# Mixer.net
KiCad netlist of a schematic drawn in EasyEDA Pro
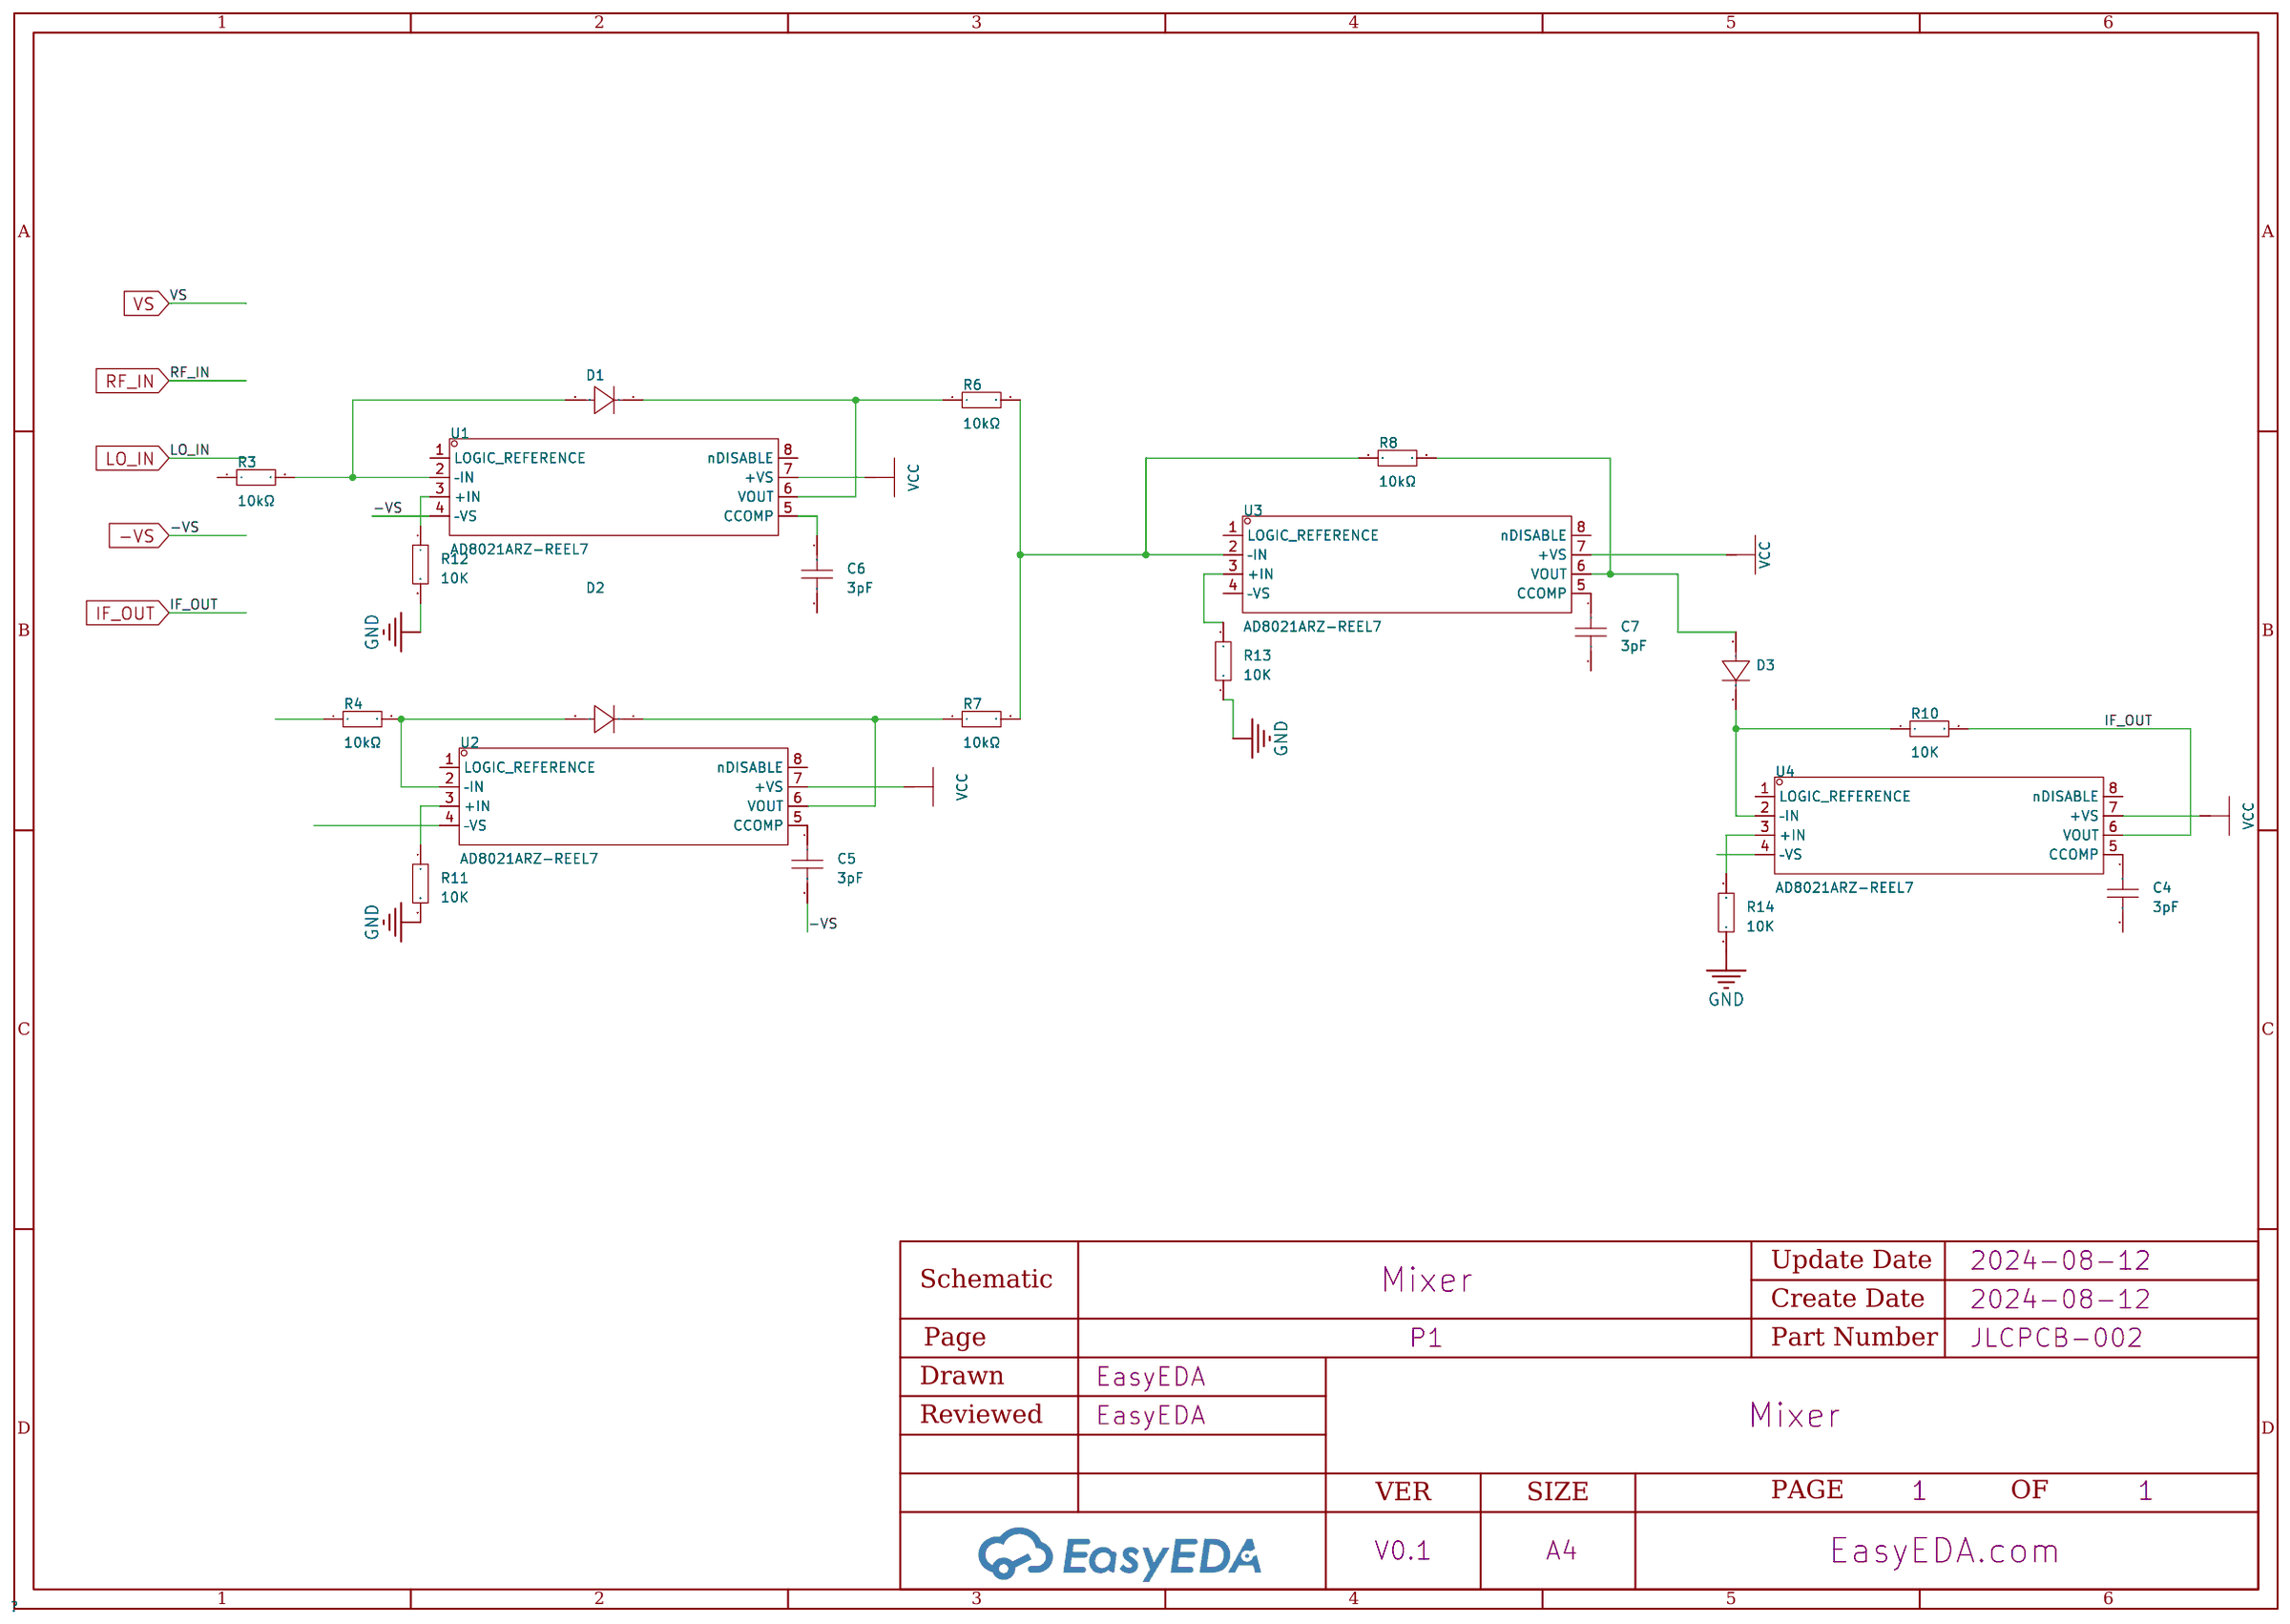
[diagram p0: schematic sheet]

(export (version "E")
  (design (tool "Eeschema 10.0.6"))
  (components
    (comp (ref "C4") (value "3pF") (footprint "easyedapro:C0201") (libsource (lib "easyedapro") (part "CAP")))
    (comp (ref "C5") (value "3pF") (footprint "easyedapro:C0201") (libsource (lib "easyedapro") (part "CAP")))
    (comp (ref "C6") (value "3pF") (footprint "easyedapro:C0201") (libsource (lib "easyedapro") (part "CAP")))
    (comp (ref "C7") (value "3pF") (footprint "easyedapro:C0201") (libsource (lib "easyedapro") (part "CAP")))
    (comp (ref "D1")
      (value "~")
      (footprint "easyedapro:DO-41_BD2.4-L4.7-P8.70-D0.9-RD")
      (libsource (lib "easyedapro") (part "D_1N4007"))
    )
    (comp (ref "D2")
      (value "~")
      (footprint "easyedapro:DO-41_BD2.4-L4.7-P8.70-D0.9-RD")
      (libsource (lib "easyedapro") (part "D_1N4007"))
    )
    (comp (ref "D3")
      (value "~")
      (footprint "easyedapro:DO-41_BD2.4-L4.7-P8.70-D0.9-RD")
      (libsource (lib "easyedapro") (part "D_1N4007"))
    )
    (comp (ref "R3")
      (value "10kΩ")
      (footprint "easyedapro:RES-TH_BD1.8-L3.2-P7.20-D0.4")
      (libsource (lib "easyedapro") (part "Res"))
    )
    (comp (ref "R4")
      (value "10kΩ")
      (footprint "easyedapro:RES-TH_BD1.8-L3.2-P7.20-D0.4")
      (libsource (lib "easyedapro") (part "Res"))
    )
    (comp (ref "R6")
      (value "10kΩ")
      (footprint "easyedapro:RES-TH_BD1.8-L3.2-P7.20-D0.4")
      (libsource (lib "easyedapro") (part "Res"))
    )
    (comp (ref "R7")
      (value "10kΩ")
      (footprint "easyedapro:RES-TH_BD1.8-L3.2-P7.20-D0.4")
      (libsource (lib "easyedapro") (part "Res"))
    )
    (comp (ref "R8")
      (value "10kΩ")
      (footprint "easyedapro:RES-TH_BD1.8-L3.2-P7.20-D0.4")
      (libsource (lib "easyedapro") (part "Res"))
    )
    (comp (ref "R10")
      (value "10K")
      (footprint "easyedapro:R0603")
      (libsource (lib "easyedapro") (part "Res"))
    )
    (comp (ref "R11")
      (value "10K")
      (footprint "easyedapro:RES-TH_BD1.8-L3.2-P7.20-D0.4")
      (libsource (lib "easyedapro") (part "Res"))
    )
    (comp (ref "R12")
      (value "10K")
      (footprint "easyedapro:RES-TH_BD1.8-L3.2-P7.20-D0.4")
      (libsource (lib "easyedapro") (part "Res"))
    )
    (comp (ref "R13")
      (value "10K")
      (footprint "easyedapro:RES-TH_BD1.8-L3.2-P7.20-D0.4")
      (libsource (lib "easyedapro") (part "Res"))
    )
    (comp (ref "R14")
      (value "10K")
      (footprint "easyedapro:RES-TH_BD1.8-L3.2-P7.20-D0.4")
      (libsource (lib "easyedapro") (part "Res"))
    )
    (comp (ref "U1")
      (value "AD8021ARZ-REEL7")
      (footprint "easyedapro:SOIC-8_L4.9-W3.9-P1.27-LS6.0-BL-2")
      (fields (field (name "Manufacturer") "ADI(亚德诺)"))
      (libsource (lib "easyedapro") (part "AD8021ARZ"))
    )
    (comp (ref "U2")
      (value "AD8021ARZ-REEL7")
      (footprint "easyedapro:SOIC-8_L4.9-W3.9-P1.27-LS6.0-BL-2")
      (fields (field (name "Manufacturer") "ADI(亚德诺)"))
      (libsource (lib "easyedapro") (part "AD8021ARZ"))
    )
    (comp (ref "U3")
      (value "AD8021ARZ-REEL7")
      (footprint "easyedapro:SOIC-8_L4.9-W3.9-P1.27-LS6.0-BL-2")
      (fields (field (name "Manufacturer") "ADI(亚德诺)"))
      (libsource (lib "easyedapro") (part "AD8021ARZ"))
    )
    (comp (ref "U4")
      (value "AD8021ARZ-REEL7")
      (footprint "easyedapro:SOIC-8_L4.9-W3.9-P1.27-LS6.0-BL-2")
      (fields (field (name "Manufacturer") "ADI(亚德诺)"))
      (libsource (lib "easyedapro") (part "AD8021ARZ"))
    )
  )
  (nets
    (net (code "1") (name "-VS") (class "Default")
      (node (ref "C5") (pin "2") (pinfunction "2_2") (pintype "input"))
      (node (ref "U1") (pin "4") (pinfunction "–VS_4") (pintype "unspecified"))
    )
    (net (code "2") (name "GND") (class "Default")
      (node (ref "R11") (pin "2") (pinfunction "2_2") (pintype "input"))
      (node (ref "R12") (pin "2") (pinfunction "2_2") (pintype "input"))
      (node (ref "R13") (pin "1") (pinfunction "1_1") (pintype "input"))
      (node (ref "R14") (pin "1") (pinfunction "1_1") (pintype "input"))
    )
    (net (code "3") (name "IF_OUT") (class "Default")
      (node (ref "R10") (pin "2") (pinfunction "2_2") (pintype "input"))
      (node (ref "U4") (pin "6") (pinfunction "VOUT_6") (pintype "unspecified"))
    )
    (net (code "5") (name "Net-(D1-A)") (class "Default")
      (node (ref "D1") (pin "2") (pinfunction "A_2") (pintype "input"))
      (node (ref "R3") (pin "2") (pinfunction "2_2") (pintype "input"))
      (node (ref "U1") (pin "2") (pinfunction "–IN_2") (pintype "unspecified"))
    )
    (net (code "6") (name "Net-(D1-K)") (class "Default")
      (node (ref "D1") (pin "1") (pinfunction "K_1") (pintype "input"))
      (node (ref "R6") (pin "1") (pinfunction "1_1") (pintype "input"))
      (node (ref "U1") (pin "6") (pinfunction "VOUT_6") (pintype "unspecified"))
    )
    (net (code "7") (name "Net-(D2-A)") (class "Default")
      (node (ref "D2") (pin "2") (pinfunction "A_2") (pintype "input"))
      (node (ref "R4") (pin "2") (pinfunction "2_2") (pintype "input"))
      (node (ref "U2") (pin "2") (pinfunction "–IN_2") (pintype "unspecified"))
    )
    (net (code "8") (name "Net-(D2-K)") (class "Default")
      (node (ref "D2") (pin "1") (pinfunction "K_1") (pintype "input"))
      (node (ref "R7") (pin "1") (pinfunction "1_1") (pintype "input"))
      (node (ref "U2") (pin "6") (pinfunction "VOUT_6") (pintype "unspecified"))
    )
    (net (code "9") (name "Net-(D3-A)") (class "Default")
      (node (ref "D3") (pin "2") (pinfunction "A_2") (pintype "input"))
      (node (ref "R8") (pin "2") (pinfunction "2_2") (pintype "input"))
      (node (ref "U3") (pin "6") (pinfunction "VOUT_6") (pintype "unspecified"))
    )
    (net (code "10") (name "Net-(D3-K)") (class "Default")
      (node (ref "D3") (pin "1") (pinfunction "K_1") (pintype "input"))
      (node (ref "R10") (pin "1") (pinfunction "1_1") (pintype "input"))
      (node (ref "U4") (pin "2") (pinfunction "–IN_2") (pintype "unspecified"))
    )
    (net (code "11") (name "Net-(U1-+IN)") (class "Default")
      (node (ref "R12") (pin "1") (pinfunction "1_1") (pintype "input"))
      (node (ref "U1") (pin "3") (pinfunction "+IN_3") (pintype "unspecified"))
    )
    (net (code "12") (name "Net-(U1-CCOMP)") (class "Default")
      (node (ref "C6") (pin "1") (pinfunction "1_1") (pintype "input"))
      (node (ref "U1") (pin "5") (pinfunction "CCOMP_5") (pintype "unspecified"))
    )
    (net (code "13") (name "Net-(U2-+IN)") (class "Default")
      (node (ref "R11") (pin "1") (pinfunction "1_1") (pintype "input"))
      (node (ref "U2") (pin "3") (pinfunction "+IN_3") (pintype "unspecified"))
    )
    (net (code "14") (name "Net-(U2-CCOMP)") (class "Default")
      (node (ref "C5") (pin "1") (pinfunction "1_1") (pintype "input"))
      (node (ref "U2") (pin "5") (pinfunction "CCOMP_5") (pintype "unspecified"))
    )
    (net (code "15") (name "Net-(U3-+IN)") (class "Default")
      (node (ref "R13") (pin "2") (pinfunction "2_2") (pintype "input"))
      (node (ref "U3") (pin "3") (pinfunction "+IN_3") (pintype "unspecified"))
    )
    (net (code "16") (name "Net-(U3-CCOMP)") (class "Default")
      (node (ref "C7") (pin "1") (pinfunction "1_1") (pintype "input"))
      (node (ref "U3") (pin "5") (pinfunction "CCOMP_5") (pintype "unspecified"))
    )
    (net (code "17") (name "Net-(U3-–IN)") (class "Default")
      (node (ref "R6") (pin "2") (pinfunction "2_2") (pintype "input"))
      (node (ref "R7") (pin "2") (pinfunction "2_2") (pintype "input"))
      (node (ref "R8") (pin "1") (pinfunction "1_1") (pintype "input"))
      (node (ref "U3") (pin "2") (pinfunction "–IN_2") (pintype "unspecified"))
    )
    (net (code "18") (name "Net-(U4-+IN)") (class "Default")
      (node (ref "R14") (pin "2") (pinfunction "2_2") (pintype "input"))
      (node (ref "U4") (pin "3") (pinfunction "+IN_3") (pintype "unspecified"))
    )
    (net (code "19") (name "Net-(U4-CCOMP)") (class "Default")
      (node (ref "C4") (pin "1") (pinfunction "1_1") (pintype "input"))
      (node (ref "U4") (pin "5") (pinfunction "CCOMP_5") (pintype "unspecified"))
    )
    (net (code "21") (name "VCC") (class "Default")
      (node (ref "U1") (pin "7") (pinfunction "+VS_7") (pintype "unspecified"))
      (node (ref "U2") (pin "7") (pinfunction "+VS_7") (pintype "unspecified"))
      (node (ref "U3") (pin "7") (pinfunction "+VS_7") (pintype "unspecified"))
      (node (ref "U4") (pin "7") (pinfunction "+VS_7") (pintype "unspecified"))
    )
    (net (code "23") (name "unconnected-(C4-Pad2)") (class "Default")
      (node (ref "C4") (pin "2") (pinfunction "2_2") (pintype "input"))
    )
    (net (code "24") (name "unconnected-(C6-Pad2)") (class "Default")
      (node (ref "C6") (pin "2") (pinfunction "2_2") (pintype "input"))
    )
    (net (code "25") (name "unconnected-(C7-Pad2)") (class "Default")
      (node (ref "C7") (pin "2") (pinfunction "2_2") (pintype "input"))
    )
    (net (code "26") (name "unconnected-(R3-Pad1)") (class "Default")
      (node (ref "R3") (pin "1") (pinfunction "1_1") (pintype "input"))
    )
    (net (code "27") (name "unconnected-(R4-Pad1)") (class "Default")
      (node (ref "R4") (pin "1") (pinfunction "1_1") (pintype "input"))
    )
    (net (code "28") (name "unconnected-(U1-LOGIC_REFERENCE-Pad1)") (class "Default")
      (node (ref "U1") (pin "1") (pinfunction "LOGIC_REFERENCE_1") (pintype "unspecified"))
    )
    (net (code "29") (name "unconnected-(U1-nDISABLE-Pad8)") (class "Default")
      (node (ref "U1") (pin "8") (pinfunction "nDISABLE_8") (pintype "unspecified"))
    )
    (net (code "30") (name "unconnected-(U2-LOGIC_REFERENCE-Pad1)") (class "Default")
      (node (ref "U2") (pin "1") (pinfunction "LOGIC_REFERENCE_1") (pintype "unspecified"))
    )
    (net (code "31") (name "unconnected-(U2-nDISABLE-Pad8)") (class "Default")
      (node (ref "U2") (pin "8") (pinfunction "nDISABLE_8") (pintype "unspecified"))
    )
    (net (code "32") (name "unconnected-(U2-–VS-Pad4)") (class "Default")
      (node (ref "U2") (pin "4") (pinfunction "–VS_4") (pintype "unspecified"))
    )
    (net (code "33") (name "unconnected-(U3-LOGIC_REFERENCE-Pad1)") (class "Default")
      (node (ref "U3") (pin "1") (pinfunction "LOGIC_REFERENCE_1") (pintype "unspecified"))
    )
    (net (code "34") (name "unconnected-(U3-nDISABLE-Pad8)") (class "Default")
      (node (ref "U3") (pin "8") (pinfunction "nDISABLE_8") (pintype "unspecified"))
    )
    (net (code "35") (name "unconnected-(U3-–VS-Pad4)") (class "Default")
      (node (ref "U3") (pin "4") (pinfunction "–VS_4") (pintype "unspecified"))
    )
    (net (code "36") (name "unconnected-(U4-LOGIC_REFERENCE-Pad1)") (class "Default")
      (node (ref "U4") (pin "1") (pinfunction "LOGIC_REFERENCE_1") (pintype "unspecified"))
    )
    (net (code "37") (name "unconnected-(U4-nDISABLE-Pad8)") (class "Default")
      (node (ref "U4") (pin "8") (pinfunction "nDISABLE_8") (pintype "unspecified"))
    )
    (net (code "38") (name "unconnected-(U4-–VS-Pad4)") (class "Default")
      (node (ref "U4") (pin "4") (pinfunction "–VS_4") (pintype "unspecified"))
    )
  )
)
